# hd-gs-alt.net
KiCad netlist of a schematic drawn in Altium Designer
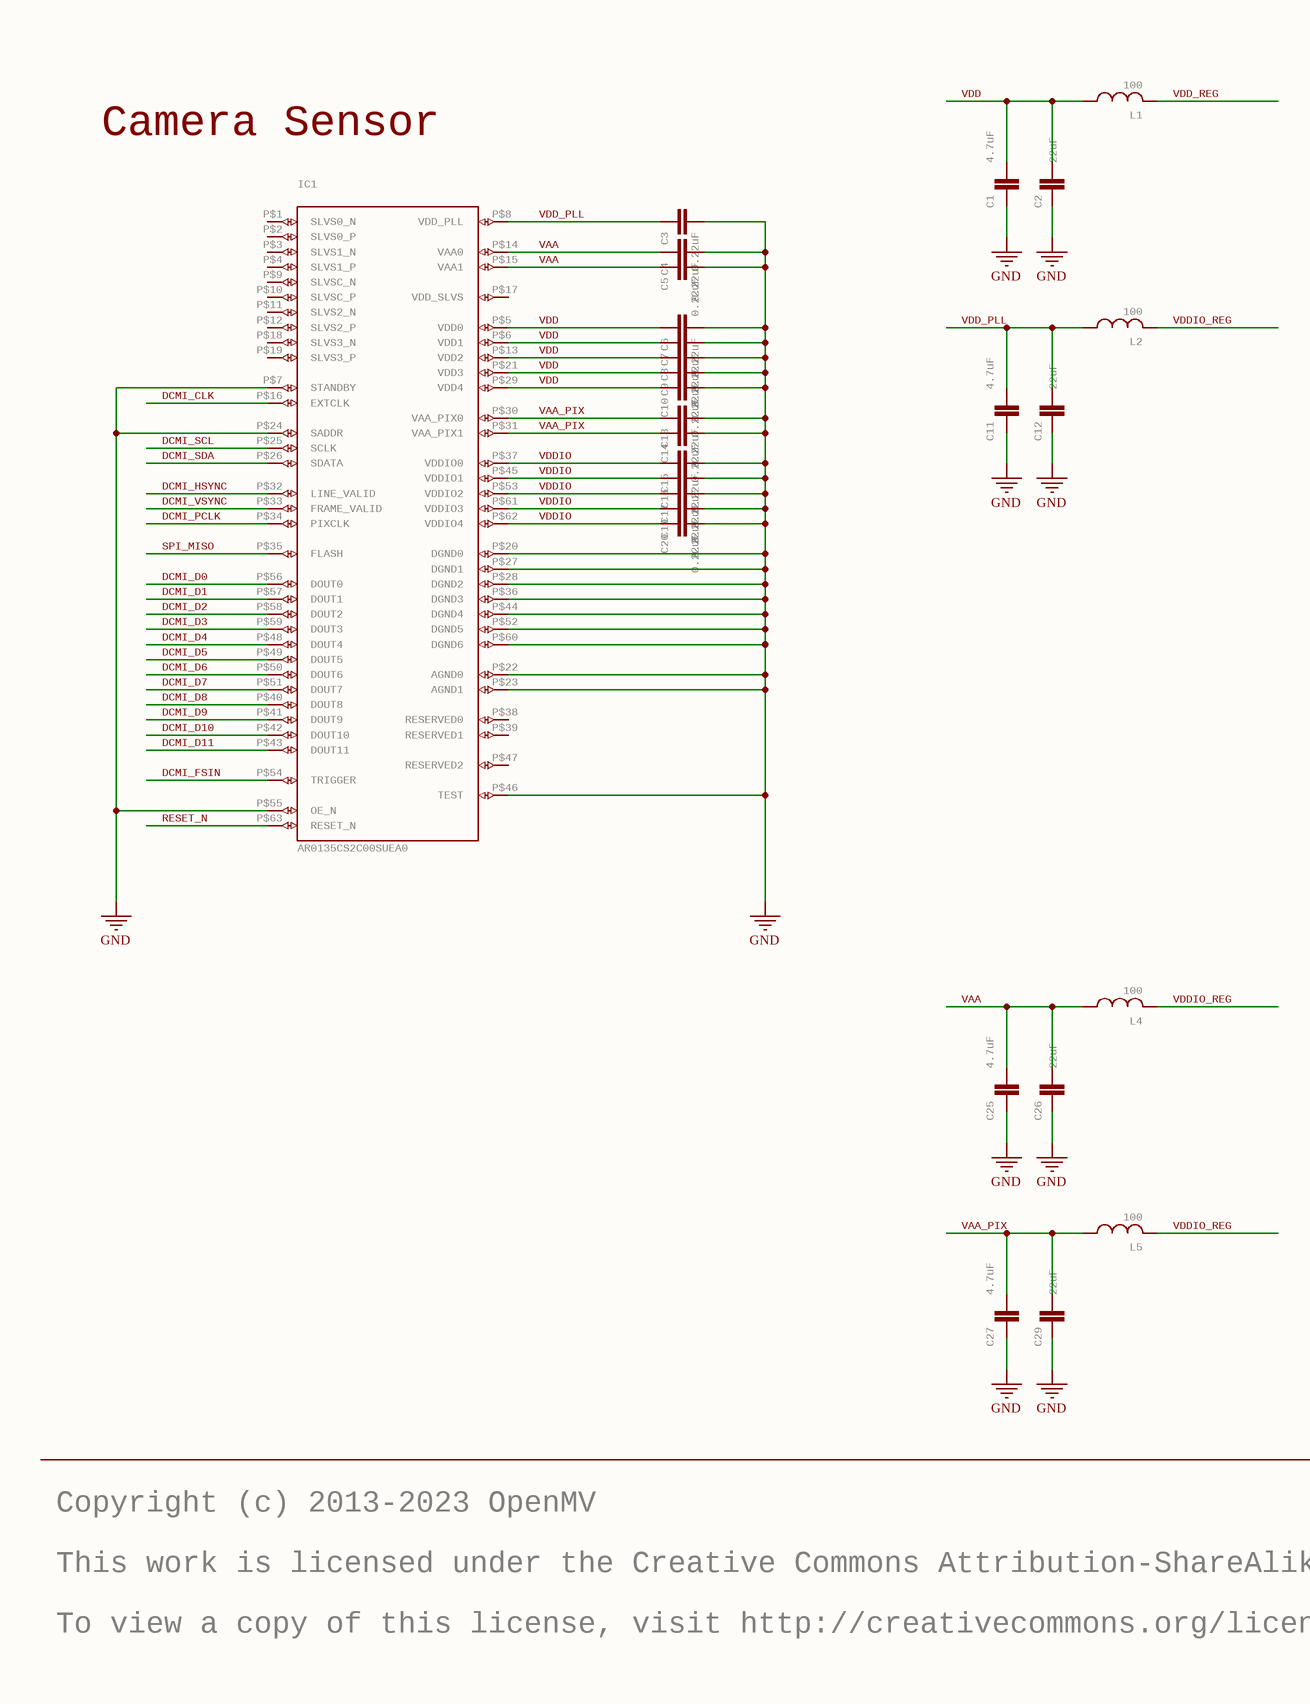
[diagram p0: hd-gs-alt.SchDoc, left]
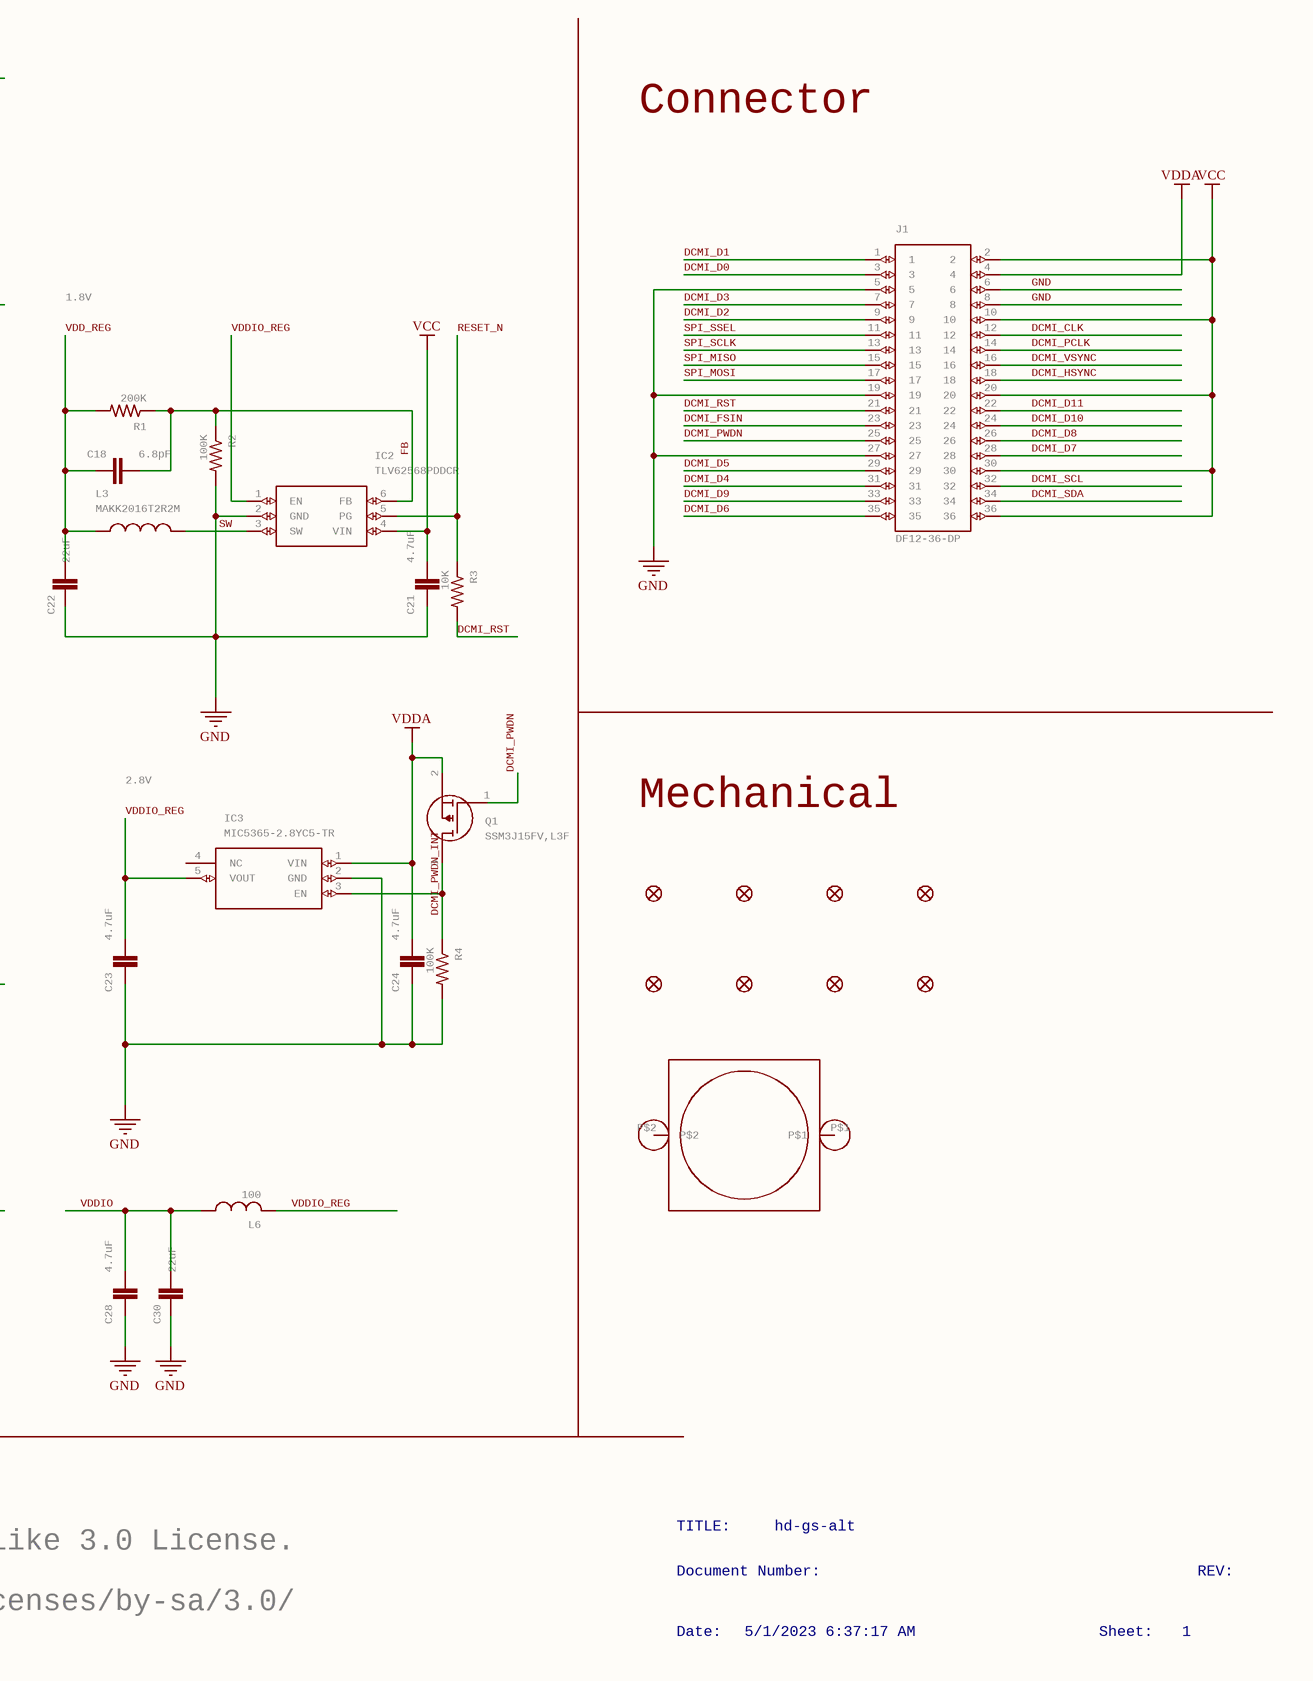
[diagram p1: hd-gs-alt.SchDoc, right]

(export (version "E")
  (design (tool "Eeschema 10.0.6"))
  (components
    (comp (ref "C1")
      (value "4.7uF")
      (footprint "0402")
      (description "0402 (1005 Metric) Nick Garner - TeleSense")
      (fields (field (name "MPN") "JMK105BBJ475MV-F"))
      (libsource (lib "camera-modules") (part "CAP_0402"))
    )
    (comp (ref "C2")
      (value "22uF")
      (footprint "0805")
      (fields (field (name "MPN") "CL21A226MQQNNNE"))
      (libsource (lib "camera-modules") (part "22UF-0805-6.3V-20%"))
    )
    (comp (ref "C3")
      (value "0.22uF")
      (footprint "C0201")
      (description "CAPACITOR, European symbol")
      (fields (field (name "MPN") "GRM033R60J224ME15D"))
      (libsource (lib "camera-modules") (part "C-EUC0201"))
    )
    (comp (ref "C4")
      (value "0.22uF")
      (footprint "C0201")
      (description "CAPACITOR, European symbol")
      (fields (field (name "MPN") "GRM033R60J224ME15D"))
      (libsource (lib "camera-modules") (part "C-EUC0201"))
    )
    (comp (ref "C5")
      (value "0.22uF")
      (footprint "C0201")
      (description "CAPACITOR, European symbol")
      (fields (field (name "MPN") "GRM033R60J224ME15D"))
      (libsource (lib "camera-modules") (part "C-EUC0201"))
    )
    (comp (ref "C6")
      (value "0.22uF")
      (footprint "C0201")
      (description "CAPACITOR, European symbol")
      (fields (field (name "MPN") "GRM033R60J224ME15D"))
      (libsource (lib "camera-modules") (part "C-EUC0201"))
    )
    (comp (ref "C7")
      (value "0.22uF")
      (footprint "C0201")
      (description "CAPACITOR, European symbol")
      (fields (field (name "MPN") "GRM033R60J224ME15D"))
      (libsource (lib "camera-modules") (part "C-EUC0201"))
    )
    (comp (ref "C8")
      (value "0.22uF")
      (footprint "C0201")
      (description "CAPACITOR, European symbol")
      (fields (field (name "MPN") "GRM033R60J224ME15D"))
      (libsource (lib "camera-modules") (part "C-EUC0201"))
    )
    (comp (ref "C9")
      (value "0.22uF")
      (footprint "C0201")
      (description "CAPACITOR, European symbol")
      (fields (field (name "MPN") "GRM033R60J224ME15D"))
      (libsource (lib "camera-modules") (part "C-EUC0201"))
    )
    (comp (ref "C10")
      (value "0.22uF")
      (footprint "C0201")
      (description "CAPACITOR, European symbol")
      (fields (field (name "MPN") "GRM033R60J224ME15D"))
      (libsource (lib "camera-modules") (part "C-EUC0201"))
    )
    (comp (ref "C11")
      (value "4.7uF")
      (footprint "0402")
      (description "0402 (1005 Metric) Nick Garner - TeleSense")
      (fields (field (name "MPN") "JMK105BBJ475MV-F"))
      (libsource (lib "camera-modules") (part "CAP_0402"))
    )
    (comp (ref "C12")
      (value "22uF")
      (footprint "0805")
      (fields (field (name "MPN") "CL21A226MQQNNNE"))
      (libsource (lib "camera-modules") (part "22UF-0805-6.3V-20%"))
    )
    (comp (ref "C13")
      (value "0.22uF")
      (footprint "C0201")
      (description "CAPACITOR, European symbol")
      (fields (field (name "MPN") "GRM033R60J224ME15D"))
      (libsource (lib "camera-modules") (part "C-EUC0201"))
    )
    (comp (ref "C14")
      (value "0.22uF")
      (footprint "C0201")
      (description "CAPACITOR, European symbol")
      (fields (field (name "MPN") "GRM033R60J224ME15D"))
      (libsource (lib "camera-modules") (part "C-EUC0201"))
    )
    (comp (ref "C15")
      (value "0.22uF")
      (footprint "C0201")
      (description "CAPACITOR, European symbol")
      (fields (field (name "MPN") "GRM033R60J224ME15D"))
      (libsource (lib "camera-modules") (part "C-EUC0201"))
    )
    (comp (ref "C16")
      (value "0.22uF")
      (footprint "C0201")
      (description "CAPACITOR, European symbol")
      (fields (field (name "MPN") "GRM033R60J224ME15D"))
      (libsource (lib "camera-modules") (part "C-EUC0201"))
    )
    (comp (ref "C17")
      (value "0.22uF")
      (footprint "C0201")
      (description "CAPACITOR, European symbol")
      (fields (field (name "MPN") "GRM033R60J224ME15D"))
      (libsource (lib "camera-modules") (part "C-EUC0201"))
    )
    (comp (ref "C18")
      (value "6.8pF")
      (footprint "0402")
      (description "0402 (1005 Metric) Nick Garner - TeleSense")
      (fields (field (name "MPN") "GRM1555C1H6R8DA01D"))
      (libsource (lib "") (part "CAP_0402_1"))
    )
    (comp (ref "C19")
      (value "0.22uF")
      (footprint "C0201")
      (description "CAPACITOR, European symbol")
      (fields (field (name "MPN") "GRM033R60J224ME15D"))
      (libsource (lib "camera-modules") (part "C-EUC0201"))
    )
    (comp (ref "C20")
      (value "0.22uF")
      (footprint "C0201")
      (description "CAPACITOR, European symbol")
      (fields (field (name "MPN") "GRM033R60J224ME15D"))
      (libsource (lib "camera-modules") (part "C-EUC0201"))
    )
    (comp (ref "C21")
      (value "4.7uF")
      (footprint "0402")
      (description "0402 (1005 Metric) Nick Garner - TeleSense")
      (fields (field (name "MPN") "JMK105BBJ475MV-F"))
      (libsource (lib "camera-modules") (part "CAP_0402"))
    )
    (comp (ref "C22")
      (value "22uF")
      (footprint "0805")
      (fields (field (name "MPN") "CL21A226MQQNNNE"))
      (libsource (lib "camera-modules") (part "22UF-0805-6.3V-20%"))
    )
    (comp (ref "C23")
      (value "4.7uF")
      (footprint "0402")
      (description "0402 (1005 Metric) Nick Garner - TeleSense")
      (fields (field (name "MPN") "JMK105BBJ475MV-F"))
      (libsource (lib "camera-modules") (part "CAP_0402"))
    )
    (comp (ref "C24")
      (value "4.7uF")
      (footprint "0402")
      (description "0402 (1005 Metric) Nick Garner - TeleSense")
      (fields (field (name "MPN") "JMK105BBJ475MV-F"))
      (libsource (lib "camera-modules") (part "CAP_0402"))
    )
    (comp (ref "C25")
      (value "4.7uF")
      (footprint "0402")
      (description "0402 (1005 Metric) Nick Garner - TeleSense")
      (fields (field (name "MPN") "JMK105BBJ475MV-F"))
      (libsource (lib "camera-modules") (part "CAP_0402"))
    )
    (comp (ref "C26")
      (value "22uF")
      (footprint "0805")
      (fields (field (name "MPN") "CL21A226MQQNNNE"))
      (libsource (lib "camera-modules") (part "22UF-0805-6.3V-20%"))
    )
    (comp (ref "C27")
      (value "4.7uF")
      (footprint "0402")
      (description "0402 (1005 Metric) Nick Garner - TeleSense")
      (fields (field (name "MPN") "JMK105BBJ475MV-F"))
      (libsource (lib "camera-modules") (part "CAP_0402"))
    )
    (comp (ref "C28")
      (value "4.7uF")
      (footprint "0402")
      (description "0402 (1005 Metric) Nick Garner - TeleSense")
      (fields (field (name "MPN") "JMK105BBJ475MV-F"))
      (libsource (lib "camera-modules") (part "CAP_0402"))
    )
    (comp (ref "C29")
      (value "22uF")
      (footprint "0805")
      (fields (field (name "MPN") "CL21A226MQQNNNE"))
      (libsource (lib "camera-modules") (part "22UF-0805-6.3V-20%"))
    )
    (comp (ref "C30")
      (value "22uF")
      (footprint "0805")
      (fields (field (name "MPN") "CL21A226MQQNNNE"))
      (libsource (lib "camera-modules") (part "22UF-0805-6.3V-20%"))
    )
    (comp (ref "FD1")
      (value "FIDUCIAL1X2")
      (footprint "FIDUCIAL-1X2")
      (fields (field (name "LIBRARYNAME") "SparkFun-Aesthetics"))
      (libsource (lib "camera-modules") (part "FIDUCIAL1X2"))
    )
    (comp (ref "FD2")
      (value "FIDUCIAL1X2")
      (footprint "FIDUCIAL-1X2")
      (fields (field (name "LIBRARYNAME") "SparkFun-Aesthetics"))
      (libsource (lib "camera-modules") (part "FIDUCIAL1X2"))
    )
    (comp (ref "FD3")
      (value "FIDUCIAL1X2")
      (footprint "FIDUCIAL-1X2")
      (fields (field (name "LIBRARYNAME") "SparkFun-Aesthetics"))
      (libsource (lib "camera-modules") (part "FIDUCIAL1X2"))
    )
    (comp (ref "FD4")
      (value "FIDUCIAL1X2")
      (footprint "FIDUCIAL-1X2")
      (fields (field (name "LIBRARYNAME") "SparkFun-Aesthetics"))
      (libsource (lib "camera-modules") (part "FIDUCIAL1X2"))
    )
    (comp (ref "FD5")
      (value "FIDUCIAL1X2")
      (footprint "FIDUCIAL-1X2")
      (fields (field (name "LIBRARYNAME") "SparkFun-Aesthetics"))
      (libsource (lib "camera-modules") (part "FIDUCIAL1X2"))
    )
    (comp (ref "FD6")
      (value "FIDUCIAL1X2")
      (footprint "FIDUCIAL-1X2")
      (fields (field (name "LIBRARYNAME") "SparkFun-Aesthetics"))
      (libsource (lib "camera-modules") (part "FIDUCIAL1X2"))
    )
    (comp (ref "FD7")
      (value "FIDUCIAL1X2")
      (footprint "FIDUCIAL-1X2")
      (fields (field (name "LIBRARYNAME") "SparkFun-Aesthetics"))
      (libsource (lib "camera-modules") (part "FIDUCIAL1X2"))
    )
    (comp (ref "FD8")
      (value "FIDUCIAL1X2")
      (footprint "FIDUCIAL-1X2")
      (fields (field (name "LIBRARYNAME") "SparkFun-Aesthetics"))
      (libsource (lib "camera-modules") (part "FIDUCIAL1X2"))
    )
    (comp (ref "H1")
      (value "LENSMOUNT20MM")
      (footprint "LENSMOUNT-20MM")
      (libsource (lib "camera-modules") (part "LENSMOUNT20MM"))
    )
    (comp (ref "IC1")
      (value "AR0135CS2C00SUEA0")
      (footprint "AR0135CS2C00SUEA0")
      (fields (field (name "MPN") "AR0135CS2C00SUEA0-DRBR"))
      (libsource (lib "camera-modules") (part "AR0135CS2C00SUEA0"))
    )
    (comp (ref "IC2")
      (value "TLV62568PDDCR")
      (footprint "SOT95P280X110-6N")
      (fields (field (name "MOUSER_PART_NUMBER") "595-TLV62568PDDCR"))
      (libsource (lib "camera-modules") (part "TLV62568PDDCR"))
    )
    (comp (ref "IC3")
      (value "MIC5365-2.8YC5-TR")
      (footprint "SOT65P210X110-5N")
      (description "IC REG LINEAR 2.8V 150MA SC70-5   Source:  Datasheet")
      (fields (field (name "MOUSER_PART_NUMBER") "998-MIC5365-2.8YC5TR"))
      (libsource (lib "camera-modules") (part "MIC5365-2.8YC5-TR"))
    )
    (comp (ref "J1")
      (value "DF12-36-DP")
      (footprint "DF12-36-DP")
      (fields (field (name "MPN") "DF12NB(3.0)-36DP-0.5V(51)"))
      (libsource (lib "camera-modules") (part "DF12-36-DP"))
    )
    (comp (ref "L1")
      (value "100")
      (footprint "0402")
      (fields (field (name "MPN") "MFBM1V1005-101-R"))
      (libsource (lib "camera-modules") (part "INDUCTOR_0402"))
    )
    (comp (ref "L2")
      (value "100")
      (footprint "0402")
      (fields (field (name "MPN") "MFBM1V1005-101-R"))
      (libsource (lib "camera-modules") (part "INDUCTOR_0402"))
    )
    (comp (ref "L3")
      (value "MAKK2016T2R2M")
      (footprint "INDC2016X100N")
      (description "INDUCTOR, METAL CORE Check availability")
      (fields (field (name "MF") "Taiyo Yuden"))
      (libsource (lib "camera-modules") (part "MAKK2016T2R2M"))
    )
    (comp (ref "L4")
      (value "100")
      (footprint "0402")
      (fields (field (name "MPN") "MFBM1V1005-101-R"))
      (libsource (lib "camera-modules") (part "INDUCTOR_0402"))
    )
    (comp (ref "L5")
      (value "100")
      (footprint "0402")
      (fields (field (name "MPN") "MFBM1V1005-101-R"))
      (libsource (lib "camera-modules") (part "INDUCTOR_0402"))
    )
    (comp (ref "L6")
      (value "100")
      (footprint "0402")
      (fields (field (name "MPN") "MFBM1V1005-101-R"))
      (libsource (lib "camera-modules") (part "INDUCTOR_0402"))
    )
    (comp (ref "Q1")
      (value "SSM3J15FV,L3F")
      (footprint "SSM3J15FV")
      (description "MOSFET 30 V, P-channel Trench MOSFET   Source:  Datasheet")
      (libsource (lib "camera-modules") (part "PMXB120EPEZ"))
    )
    (comp (ref "R1")
      (value "200K")
      (footprint "R0402")
      (description "RESISTOR, American symbol")
      (fields (field (name "MPN") "CRCW0402200KFKEDC"))
      (libsource (lib "camera-modules") (part "R-US_R0402"))
    )
    (comp (ref "R2")
      (value "100K")
      (footprint "R0402")
      (description "RESISTOR, American symbol")
      (fields (field (name "MPN") "AC0402FR-07100KL"))
      (libsource (lib "camera-modules") (part "R-US_R0402"))
    )
    (comp (ref "R3")
      (value "10K")
      (footprint "R0402")
      (description "RESISTOR, American symbol")
      (fields (field (name "MPN") "AC0402FR-1310KL"))
      (libsource (lib "camera-modules") (part "R-US_R0402"))
    )
    (comp (ref "R4")
      (value "100K")
      (footprint "R0402")
      (description "RESISTOR, American symbol")
      (fields (field (name "MPN") "AC0402FR-07100KL"))
      (libsource (lib "camera-modules") (part "R-US_R0402"))
    )
  )
  (nets
    (net (code "1") (name "/DCMI_CLK") (class "Default")
      (node (ref "IC1") (pin "P$16") (pinfunction "EXTCLK_P$16") (pintype "bidirectional"))
      (node (ref "J1") (pin "12") (pinfunction "12_12") (pintype "bidirectional"))
    )
    (net (code "2") (name "/DCMI_D0") (class "Default")
      (node (ref "IC1") (pin "P$56") (pinfunction "DOUT0_P$56") (pintype "bidirectional"))
      (node (ref "J1") (pin "3") (pinfunction "3_3") (pintype "bidirectional"))
    )
    (net (code "3") (name "/DCMI_D1") (class "Default")
      (node (ref "IC1") (pin "P$57") (pinfunction "DOUT1_P$57") (pintype "bidirectional"))
      (node (ref "J1") (pin "1") (pinfunction "1_1") (pintype "bidirectional"))
    )
    (net (code "4") (name "/DCMI_D2") (class "Default")
      (node (ref "IC1") (pin "P$58") (pinfunction "DOUT2_P$58") (pintype "bidirectional"))
      (node (ref "J1") (pin "9") (pinfunction "9_9") (pintype "bidirectional"))
    )
    (net (code "5") (name "/DCMI_D3") (class "Default")
      (node (ref "IC1") (pin "P$59") (pinfunction "DOUT3_P$59") (pintype "bidirectional"))
      (node (ref "J1") (pin "7") (pinfunction "7_7") (pintype "bidirectional"))
    )
    (net (code "6") (name "/DCMI_D4") (class "Default")
      (node (ref "IC1") (pin "P$48") (pinfunction "DOUT4_P$48") (pintype "bidirectional"))
      (node (ref "J1") (pin "31") (pinfunction "31_31") (pintype "bidirectional"))
    )
    (net (code "7") (name "/DCMI_D5") (class "Default")
      (node (ref "IC1") (pin "P$49") (pinfunction "DOUT5_P$49") (pintype "bidirectional"))
      (node (ref "J1") (pin "29") (pinfunction "29_29") (pintype "bidirectional"))
    )
    (net (code "8") (name "/DCMI_D6") (class "Default")
      (node (ref "IC1") (pin "P$50") (pinfunction "DOUT6_P$50") (pintype "bidirectional"))
      (node (ref "J1") (pin "35") (pinfunction "35_35") (pintype "bidirectional"))
    )
    (net (code "9") (name "/DCMI_D7") (class "Default")
      (node (ref "IC1") (pin "P$51") (pinfunction "DOUT7_P$51") (pintype "bidirectional"))
      (node (ref "J1") (pin "28") (pinfunction "28_28") (pintype "bidirectional"))
    )
    (net (code "10") (name "/DCMI_D8") (class "Default")
      (node (ref "IC1") (pin "P$40") (pinfunction "DOUT8_P$40") (pintype "bidirectional"))
      (node (ref "J1") (pin "26") (pinfunction "26_26") (pintype "bidirectional"))
    )
    (net (code "11") (name "/DCMI_D9") (class "Default")
      (node (ref "IC1") (pin "P$41") (pinfunction "DOUT9_P$41") (pintype "bidirectional"))
      (node (ref "J1") (pin "33") (pinfunction "33_33") (pintype "bidirectional"))
    )
    (net (code "12") (name "/DCMI_D10") (class "Default")
      (node (ref "IC1") (pin "P$42") (pinfunction "DOUT10_P$42") (pintype "bidirectional"))
      (node (ref "J1") (pin "24") (pinfunction "24_24") (pintype "bidirectional"))
    )
    (net (code "13") (name "/DCMI_D11") (class "Default")
      (node (ref "IC1") (pin "P$43") (pinfunction "DOUT11_P$43") (pintype "bidirectional"))
      (node (ref "J1") (pin "22") (pinfunction "22_22") (pintype "bidirectional"))
    )
    (net (code "14") (name "/DCMI_FSIN") (class "Default")
      (node (ref "IC1") (pin "P$54") (pinfunction "TRIGGER_P$54") (pintype "bidirectional"))
      (node (ref "J1") (pin "23") (pinfunction "23_23") (pintype "bidirectional"))
    )
    (net (code "15") (name "/DCMI_HSYNC") (class "Default")
      (node (ref "IC1") (pin "P$32") (pinfunction "LINE_VALID_P$32") (pintype "bidirectional"))
      (node (ref "J1") (pin "18") (pinfunction "18_18") (pintype "bidirectional"))
    )
    (net (code "16") (name "/DCMI_PCLK") (class "Default")
      (node (ref "IC1") (pin "P$34") (pinfunction "PIXCLK_P$34") (pintype "bidirectional"))
      (node (ref "J1") (pin "14") (pinfunction "14_14") (pintype "bidirectional"))
    )
    (net (code "17") (name "/DCMI_PWDN") (class "Default")
      (node (ref "J1") (pin "25") (pinfunction "25_25") (pintype "bidirectional"))
      (node (ref "Q1") (pin "1") (pinfunction "G_1") (pintype "bidirectional"))
    )
    (net (code "18") (name "/DCMI_PWDN_INT") (class "Default")
      (node (ref "IC3") (pin "3") (pinfunction "EN_3") (pintype "bidirectional"))
      (node (ref "Q1") (pin "3") (pinfunction "D_3") (pintype "bidirectional"))
      (node (ref "R4") (pin "1") (pinfunction "1_1") (pintype "passive"))
    )
    (net (code "19") (name "/DCMI_RST") (class "Default")
      (node (ref "J1") (pin "21") (pinfunction "21_21") (pintype "bidirectional"))
      (node (ref "R3") (pin "2") (pinfunction "2_2") (pintype "passive"))
    )
    (net (code "20") (name "/DCMI_SCL") (class "Default")
      (node (ref "IC1") (pin "P$25") (pinfunction "SCLK_P$25") (pintype "bidirectional"))
      (node (ref "J1") (pin "32") (pinfunction "32_32") (pintype "bidirectional"))
    )
    (net (code "21") (name "/DCMI_SDA") (class "Default")
      (node (ref "IC1") (pin "P$26") (pinfunction "SDATA_P$26") (pintype "bidirectional"))
      (node (ref "J1") (pin "34") (pinfunction "34_34") (pintype "bidirectional"))
    )
    (net (code "22") (name "/DCMI_VSYNC") (class "Default")
      (node (ref "IC1") (pin "P$33") (pinfunction "FRAME_VALID_P$33") (pintype "bidirectional"))
      (node (ref "J1") (pin "16") (pinfunction "16_16") (pintype "bidirectional"))
    )
    (net (code "23") (name "/FB") (class "Default")
      (node (ref "C18") (pin "2") (pinfunction "2_2") (pintype "passive"))
      (node (ref "IC2") (pin "6") (pinfunction "FB_6") (pintype "bidirectional"))
      (node (ref "R1") (pin "1") (pinfunction "1_1") (pintype "passive"))
      (node (ref "R2") (pin "1") (pinfunction "1_1") (pintype "passive"))
    )
    (net (code "24") (name "/RESET_N") (class "Default")
      (node (ref "IC1") (pin "P$63") (pinfunction "RESET_N_P$63") (pintype "bidirectional"))
      (node (ref "IC2") (pin "5") (pinfunction "PG_5") (pintype "bidirectional"))
      (node (ref "R3") (pin "1") (pinfunction "1_1") (pintype "passive"))
    )
    (net (code "25") (name "/SPI_MISO") (class "Default")
      (node (ref "IC1") (pin "P$35") (pinfunction "FLASH_P$35") (pintype "bidirectional"))
      (node (ref "J1") (pin "15") (pinfunction "15_15") (pintype "bidirectional"))
    )
    (net (code "26") (name "/SPI_MOSI") (class "Default")
      (node (ref "J1") (pin "17") (pinfunction "17_17") (pintype "bidirectional"))
    )
    (net (code "27") (name "/SPI_SCLK") (class "Default")
      (node (ref "J1") (pin "13") (pinfunction "13_13") (pintype "bidirectional"))
    )
    (net (code "28") (name "/SPI_SSEL") (class "Default")
      (node (ref "J1") (pin "11") (pinfunction "11_11") (pintype "bidirectional"))
    )
    (net (code "29") (name "/SW") (class "Default")
      (node (ref "IC2") (pin "3") (pinfunction "SW_3") (pintype "bidirectional"))
      (node (ref "L3") (pin "2") (pinfunction "2_2") (pintype "passive"))
    )
    (net (code "30") (name "/VAA") (class "Default")
      (node (ref "C25") (pin "2") (pinfunction "2_2") (pintype "passive"))
      (node (ref "C26") (pin "2") (pinfunction "2_2") (pintype "passive"))
      (node (ref "C4") (pin "1") (pinfunction "1_1") (pintype "passive"))
      (node (ref "C5") (pin "1") (pinfunction "1_1") (pintype "passive"))
      (node (ref "IC1") (pin "P$14") (pinfunction "VAA0_P$14") (pintype "bidirectional"))
      (node (ref "IC1") (pin "P$15") (pinfunction "VAA1_P$15") (pintype "bidirectional"))
      (node (ref "L4") (pin "1") (pinfunction "P$1_1") (pintype "passive"))
    )
    (net (code "31") (name "/VAA_PIX") (class "Default")
      (node (ref "C13") (pin "1") (pinfunction "1_1") (pintype "passive"))
      (node (ref "C14") (pin "1") (pinfunction "1_1") (pintype "passive"))
      (node (ref "C27") (pin "2") (pinfunction "2_2") (pintype "passive"))
      (node (ref "C29") (pin "2") (pinfunction "2_2") (pintype "passive"))
      (node (ref "IC1") (pin "P$30") (pinfunction "VAA_PIX0_P$30") (pintype "bidirectional"))
      (node (ref "IC1") (pin "P$31") (pinfunction "VAA_PIX1_P$31") (pintype "bidirectional"))
      (node (ref "L5") (pin "1") (pinfunction "P$1_1") (pintype "passive"))
    )
    (net (code "32") (name "/VDD") (class "Default")
      (node (ref "C1") (pin "2") (pinfunction "2_2") (pintype "passive"))
      (node (ref "C10") (pin "1") (pinfunction "1_1") (pintype "passive"))
      (node (ref "C2") (pin "2") (pinfunction "2_2") (pintype "passive"))
      (node (ref "C6") (pin "1") (pinfunction "1_1") (pintype "passive"))
      (node (ref "C7") (pin "1") (pinfunction "1_1") (pintype "passive"))
      (node (ref "C8") (pin "1") (pinfunction "1_1") (pintype "passive"))
      (node (ref "C9") (pin "1") (pinfunction "1_1") (pintype "passive"))
      (node (ref "IC1") (pin "P$13") (pinfunction "VDD2_P$13") (pintype "bidirectional"))
      (node (ref "IC1") (pin "P$21") (pinfunction "VDD3_P$21") (pintype "bidirectional"))
      (node (ref "IC1") (pin "P$29") (pinfunction "VDD4_P$29") (pintype "bidirectional"))
      (node (ref "IC1") (pin "P$5") (pinfunction "VDD0_P$5") (pintype "bidirectional"))
      (node (ref "IC1") (pin "P$6") (pinfunction "VDD1_P$6") (pintype "bidirectional"))
      (node (ref "L1") (pin "1") (pinfunction "P$1_1") (pintype "passive"))
    )
    (net (code "33") (name "/VDDIO") (class "Default")
      (node (ref "C15") (pin "1") (pinfunction "1_1") (pintype "passive"))
      (node (ref "C16") (pin "1") (pinfunction "1_1") (pintype "passive"))
      (node (ref "C17") (pin "1") (pinfunction "1_1") (pintype "passive"))
      (node (ref "C19") (pin "1") (pinfunction "1_1") (pintype "passive"))
      (node (ref "C20") (pin "1") (pinfunction "1_1") (pintype "passive"))
      (node (ref "C28") (pin "2") (pinfunction "2_2") (pintype "passive"))
      (node (ref "C30") (pin "2") (pinfunction "2_2") (pintype "passive"))
      (node (ref "IC1") (pin "P$37") (pinfunction "VDDIO0_P$37") (pintype "bidirectional"))
      (node (ref "IC1") (pin "P$45") (pinfunction "VDDIO1_P$45") (pintype "bidirectional"))
      (node (ref "IC1") (pin "P$53") (pinfunction "VDDIO2_P$53") (pintype "bidirectional"))
      (node (ref "IC1") (pin "P$61") (pinfunction "VDDIO3_P$61") (pintype "bidirectional"))
      (node (ref "IC1") (pin "P$62") (pinfunction "VDDIO4_P$62") (pintype "bidirectional"))
      (node (ref "L6") (pin "1") (pinfunction "P$1_1") (pintype "passive"))
    )
    (net (code "34") (name "/VDDIO_REG") (class "Default")
      (node (ref "C23") (pin "2") (pinfunction "2_2") (pintype "passive"))
      (node (ref "IC2") (pin "1") (pinfunction "EN_1") (pintype "bidirectional"))
      (node (ref "IC3") (pin "5") (pinfunction "VOUT_5") (pintype "bidirectional"))
      (node (ref "L2") (pin "2") (pinfunction "P$2_2") (pintype "passive"))
      (node (ref "L4") (pin "2") (pinfunction "P$2_2") (pintype "passive"))
      (node (ref "L5") (pin "2") (pinfunction "P$2_2") (pintype "passive"))
      (node (ref "L6") (pin "2") (pinfunction "P$2_2") (pintype "passive"))
    )
    (net (code "35") (name "/VDD_PLL") (class "Default")
      (node (ref "C11") (pin "2") (pinfunction "2_2") (pintype "passive"))
      (node (ref "C12") (pin "2") (pinfunction "2_2") (pintype "passive"))
      (node (ref "C3") (pin "1") (pinfunction "1_1") (pintype "passive"))
      (node (ref "IC1") (pin "P$8") (pinfunction "VDD_PLL_P$8") (pintype "bidirectional"))
      (node (ref "L2") (pin "1") (pinfunction "P$1_1") (pintype "passive"))
    )
    (net (code "36") (name "/VDD_REG") (class "Default")
      (node (ref "C18") (pin "1") (pinfunction "1_1") (pintype "passive"))
      (node (ref "C22") (pin "2") (pinfunction "2_2") (pintype "passive"))
      (node (ref "L1") (pin "2") (pinfunction "P$2_2") (pintype "passive"))
      (node (ref "L3") (pin "1") (pinfunction "1_1") (pintype "passive"))
      (node (ref "R1") (pin "2") (pinfunction "2_2") (pintype "passive"))
    )
    (net (code "37") (name "GND") (class "Default")
      (node (ref "C1") (pin "1") (pinfunction "1_1") (pintype "passive"))
      (node (ref "C10") (pin "2") (pinfunction "2_2") (pintype "passive"))
      (node (ref "C11") (pin "1") (pinfunction "1_1") (pintype "passive"))
      (node (ref "C12") (pin "1") (pinfunction "1_1") (pintype "passive"))
      (node (ref "C13") (pin "2") (pinfunction "2_2") (pintype "passive"))
      (node (ref "C14") (pin "2") (pinfunction "2_2") (pintype "passive"))
      (node (ref "C15") (pin "2") (pinfunction "2_2") (pintype "passive"))
      (node (ref "C16") (pin "2") (pinfunction "2_2") (pintype "passive"))
      (node (ref "C17") (pin "2") (pinfunction "2_2") (pintype "passive"))
      (node (ref "C19") (pin "2") (pinfunction "2_2") (pintype "passive"))
      (node (ref "C2") (pin "1") (pinfunction "1_1") (pintype "passive"))
      (node (ref "C20") (pin "2") (pinfunction "2_2") (pintype "passive"))
      (node (ref "C21") (pin "1") (pinfunction "1_1") (pintype "passive"))
      (node (ref "C22") (pin "1") (pinfunction "1_1") (pintype "passive"))
      (node (ref "C23") (pin "1") (pinfunction "1_1") (pintype "passive"))
      (node (ref "C24") (pin "1") (pinfunction "1_1") (pintype "passive"))
      (node (ref "C25") (pin "1") (pinfunction "1_1") (pintype "passive"))
      (node (ref "C26") (pin "1") (pinfunction "1_1") (pintype "passive"))
      (node (ref "C27") (pin "1") (pinfunction "1_1") (pintype "passive"))
      (node (ref "C28") (pin "1") (pinfunction "1_1") (pintype "passive"))
      (node (ref "C29") (pin "1") (pinfunction "1_1") (pintype "passive"))
      (node (ref "C3") (pin "2") (pinfunction "2_2") (pintype "passive"))
      (node (ref "C30") (pin "1") (pinfunction "1_1") (pintype "passive"))
      (node (ref "C4") (pin "2") (pinfunction "2_2") (pintype "passive"))
      (node (ref "C5") (pin "2") (pinfunction "2_2") (pintype "passive"))
      (node (ref "C6") (pin "2") (pinfunction "2_2") (pintype "passive"))
      (node (ref "C7") (pin "2") (pinfunction "2_2") (pintype "passive"))
      (node (ref "C8") (pin "2") (pinfunction "2_2") (pintype "passive"))
      (node (ref "C9") (pin "2") (pinfunction "2_2") (pintype "passive"))
      (node (ref "IC1") (pin "P$20") (pinfunction "DGND0_P$20") (pintype "bidirectional"))
      (node (ref "IC1") (pin "P$22") (pinfunction "AGND0_P$22") (pintype "bidirectional"))
      (node (ref "IC1") (pin "P$23") (pinfunction "AGND1_P$23") (pintype "bidirectional"))
      (node (ref "IC1") (pin "P$24") (pinfunction "SADDR_P$24") (pintype "bidirectional"))
      (node (ref "IC1") (pin "P$27") (pinfunction "DGND1_P$27") (pintype "bidirectional"))
      (node (ref "IC1") (pin "P$28") (pinfunction "DGND2_P$28") (pintype "bidirectional"))
      (node (ref "IC1") (pin "P$36") (pinfunction "DGND3_P$36") (pintype "bidirectional"))
      (node (ref "IC1") (pin "P$44") (pinfunction "DGND4_P$44") (pintype "bidirectional"))
      (node (ref "IC1") (pin "P$46") (pinfunction "TEST_P$46") (pintype "bidirectional"))
      (node (ref "IC1") (pin "P$52") (pinfunction "DGND5_P$52") (pintype "bidirectional"))
      (node (ref "IC1") (pin "P$55") (pinfunction "OE_N_P$55") (pintype "bidirectional"))
      (node (ref "IC1") (pin "P$60") (pinfunction "DGND6_P$60") (pintype "bidirectional"))
      (node (ref "IC1") (pin "P$7") (pinfunction "STANDBY_P$7") (pintype "bidirectional"))
      (node (ref "IC2") (pin "2") (pinfunction "GND_2") (pintype "bidirectional"))
      (node (ref "IC3") (pin "2") (pinfunction "GND_2") (pintype "bidirectional"))
      (node (ref "J1") (pin "19") (pinfunction "19_19") (pintype "bidirectional"))
      (node (ref "J1") (pin "27") (pinfunction "27_27") (pintype "bidirectional"))
      (node (ref "J1") (pin "5") (pinfunction "5_5") (pintype "bidirectional"))
      (node (ref "J1") (pin "6") (pinfunction "6_6") (pintype "bidirectional"))
      (node (ref "J1") (pin "8") (pinfunction "8_8") (pintype "bidirectional"))
      (node (ref "R2") (pin "2") (pinfunction "2_2") (pintype "passive"))
      (node (ref "R4") (pin "2") (pinfunction "2_2") (pintype "passive"))
    )
    (net (code "38") (name "VCC") (class "Default")
      (node (ref "C21") (pin "2") (pinfunction "2_2") (pintype "passive"))
      (node (ref "IC2") (pin "4") (pinfunction "VIN_4") (pintype "bidirectional"))
      (node (ref "J1") (pin "10") (pinfunction "10_10") (pintype "bidirectional"))
      (node (ref "J1") (pin "2") (pinfunction "2_2") (pintype "bidirectional"))
      (node (ref "J1") (pin "20") (pinfunction "20_20") (pintype "bidirectional"))
      (node (ref "J1") (pin "30") (pinfunction "30_30") (pintype "bidirectional"))
      (node (ref "J1") (pin "36") (pinfunction "36_36") (pintype "bidirectional"))
    )
    (net (code "39") (name "VDDA") (class "Default")
      (node (ref "C24") (pin "2") (pinfunction "2_2") (pintype "passive"))
      (node (ref "IC3") (pin "1") (pinfunction "VIN_1") (pintype "bidirectional"))
      (node (ref "J1") (pin "4") (pinfunction "4_4") (pintype "bidirectional"))
      (node (ref "Q1") (pin "2") (pinfunction "S_2") (pintype "bidirectional"))
    )
    (net (code "40") (name "unconnected-(H1-PadP$1)") (class "Default")
      (node (ref "H1") (pin "P$1") (pinfunction "P$1_P$1") (pintype "power_in"))
    )
    (net (code "41") (name "unconnected-(H1-PadP$2)") (class "Default")
      (node (ref "H1") (pin "P$2") (pinfunction "P$2_P$2") (pintype "power_in"))
    )
    (net (code "42") (name "unconnected-(IC1-RESERVED0-PadP$38)") (class "Default")
      (node (ref "IC1") (pin "P$38") (pinfunction "RESERVED0_P$38") (pintype "bidirectional"))
    )
    (net (code "43") (name "unconnected-(IC1-RESERVED1-PadP$39)") (class "Default")
      (node (ref "IC1") (pin "P$39") (pinfunction "RESERVED1_P$39") (pintype "bidirectional"))
    )
    (net (code "44") (name "unconnected-(IC1-RESERVED2-PadP$47)") (class "Default")
      (node (ref "IC1") (pin "P$47") (pinfunction "RESERVED2_P$47") (pintype "bidirectional"))
    )
    (net (code "45") (name "unconnected-(IC1-SLVS0_N-PadP$1)") (class "Default")
      (node (ref "IC1") (pin "P$1") (pinfunction "SLVS0_N_P$1") (pintype "bidirectional"))
    )
    (net (code "46") (name "unconnected-(IC1-SLVS0_P-PadP$2)") (class "Default")
      (node (ref "IC1") (pin "P$2") (pinfunction "SLVS0_P_P$2") (pintype "bidirectional"))
    )
    (net (code "47") (name "unconnected-(IC1-SLVS1_N-PadP$3)") (class "Default")
      (node (ref "IC1") (pin "P$3") (pinfunction "SLVS1_N_P$3") (pintype "bidirectional"))
    )
    (net (code "48") (name "unconnected-(IC1-SLVS1_P-PadP$4)") (class "Default")
      (node (ref "IC1") (pin "P$4") (pinfunction "SLVS1_P_P$4") (pintype "bidirectional"))
    )
    (net (code "49") (name "unconnected-(IC1-SLVS2_N-PadP$11)") (class "Default")
      (node (ref "IC1") (pin "P$11") (pinfunction "SLVS2_N_P$11") (pintype "bidirectional"))
    )
    (net (code "50") (name "unconnected-(IC1-SLVS2_P-PadP$12)") (class "Default")
      (node (ref "IC1") (pin "P$12") (pinfunction "SLVS2_P_P$12") (pintype "bidirectional"))
    )
    (net (code "51") (name "unconnected-(IC1-SLVS3_N-PadP$18)") (class "Default")
      (node (ref "IC1") (pin "P$18") (pinfunction "SLVS3_N_P$18") (pintype "bidirectional"))
    )
    (net (code "52") (name "unconnected-(IC1-SLVS3_P-PadP$19)") (class "Default")
      (node (ref "IC1") (pin "P$19") (pinfunction "SLVS3_P_P$19") (pintype "bidirectional"))
    )
    (net (code "53") (name "unconnected-(IC1-SLVSC_N-PadP$9)") (class "Default")
      (node (ref "IC1") (pin "P$9") (pinfunction "SLVSC_N_P$9") (pintype "bidirectional"))
    )
    (net (code "54") (name "unconnected-(IC1-SLVSC_P-PadP$10)") (class "Default")
      (node (ref "IC1") (pin "P$10") (pinfunction "SLVSC_P_P$10") (pintype "bidirectional"))
    )
    (net (code "55") (name "unconnected-(IC1-VDD_SLVS-PadP$17)") (class "Default")
      (node (ref "IC1") (pin "P$17") (pinfunction "VDD_SLVS_P$17") (pintype "bidirectional"))
    )
    (net (code "56") (name "unconnected-(IC3-NC-Pad4)") (class "Default")
      (node (ref "IC3") (pin "4") (pinfunction "NC_4") (pintype "passive"))
    )
  )
)
